# BrainA1-12n.net
KiCad netlist of a schematic drawn in EAGLE
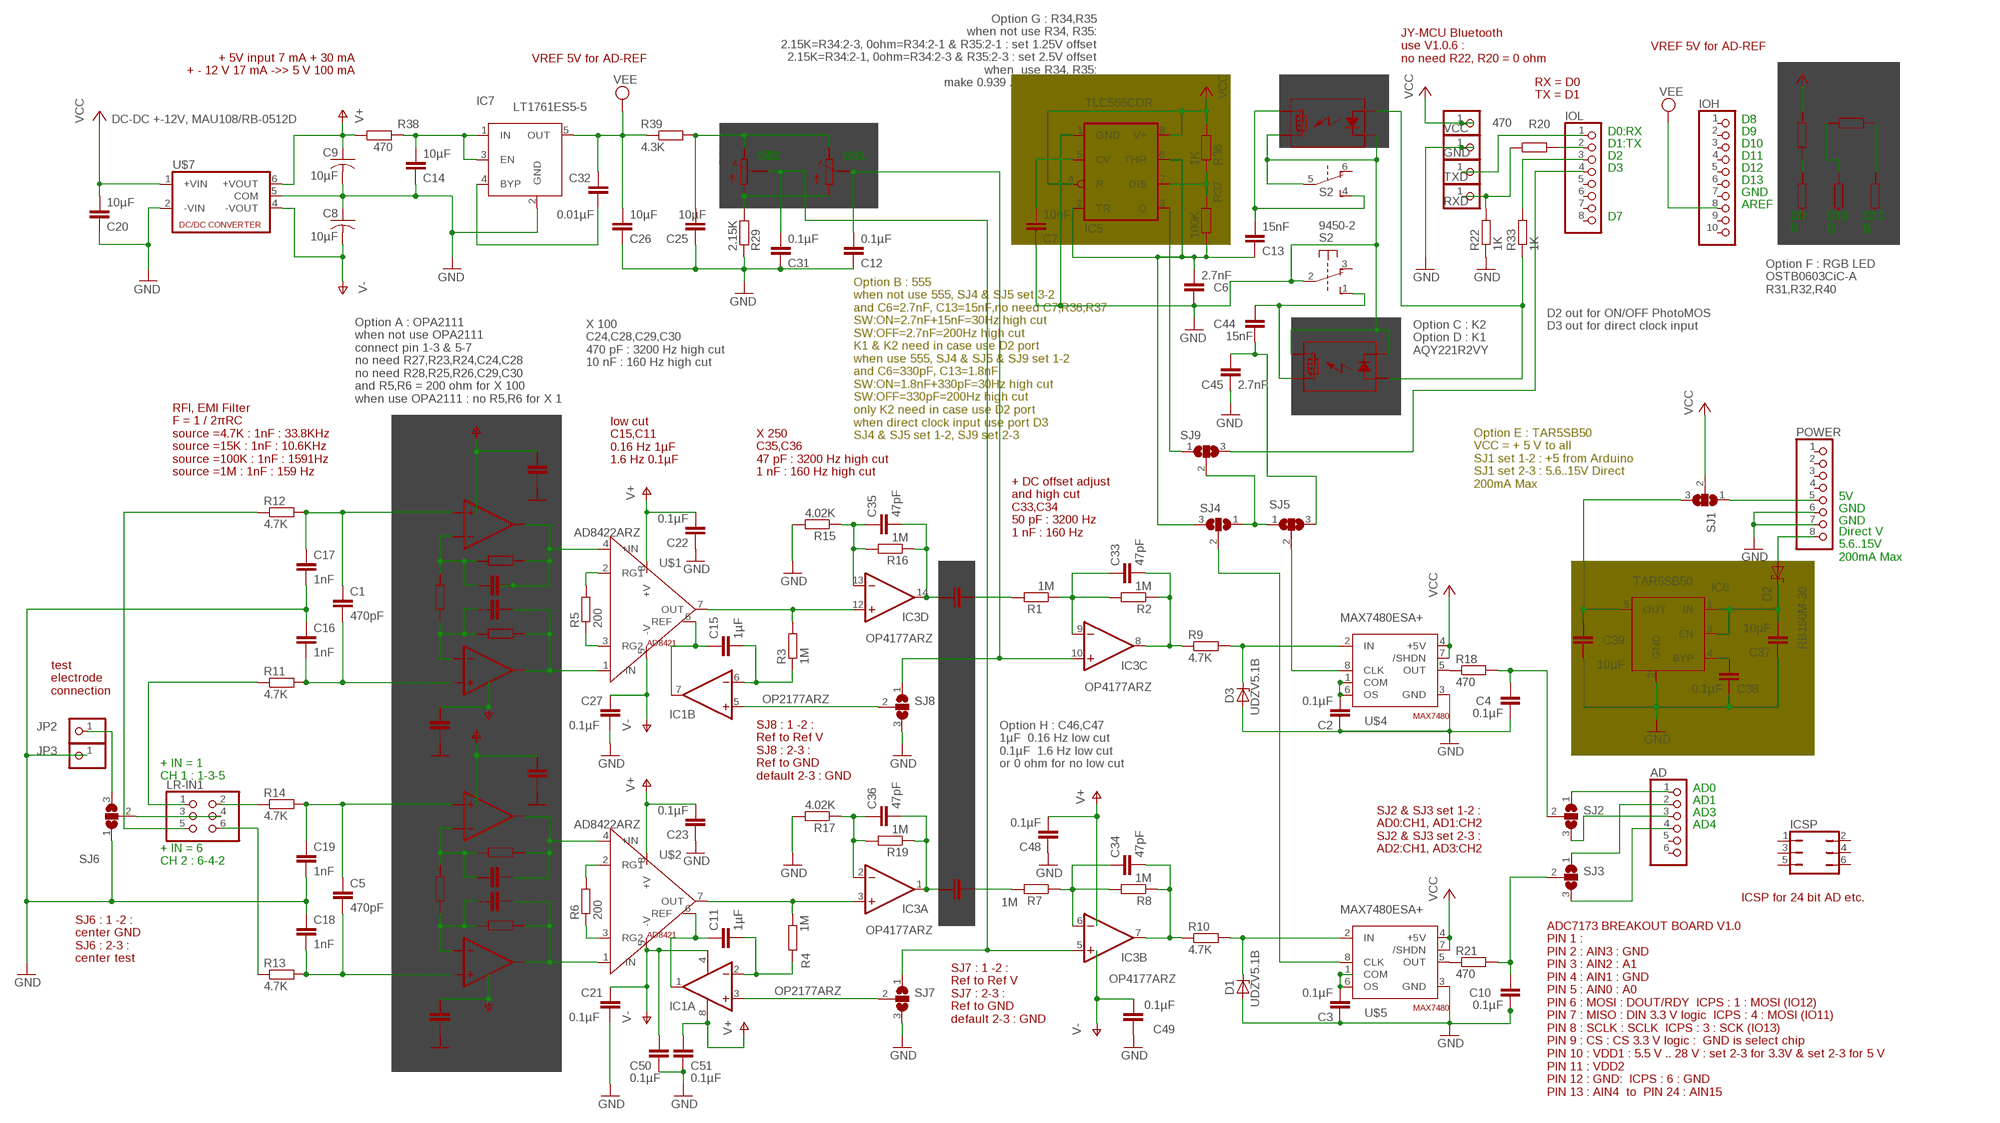
[diagram p0: schematic, sheet 1]

(export (version "E")
  (design (tool "Eeschema 10.0.6"))
  (components
    (comp (ref "AD")
      (value "PINHD-1X6")
      (footprint "eagle-import:1X06")
      (libsource (lib "eagle-import") (part "PINHD-1X6"))
    )
    (comp (ref "C1")
      (value "470pF")
      (footprint "eagle-import:C0805")
      (libsource (lib "eagle-import") (part "C-EUC0805"))
    )
    (comp (ref "C2")
      (value "0.1µF")
      (footprint "eagle-import:C0805")
      (libsource (lib "eagle-import") (part "C-EUC0805"))
    )
    (comp (ref "C3")
      (value "0.1µF")
      (footprint "eagle-import:C0805")
      (libsource (lib "eagle-import") (part "C-EUC0805"))
    )
    (comp (ref "C4")
      (value "0.1µF")
      (footprint "eagle-import:C0805")
      (libsource (lib "eagle-import") (part "C-EUC0805"))
    )
    (comp (ref "C5")
      (value "470pF")
      (footprint "eagle-import:C0805")
      (libsource (lib "eagle-import") (part "C-EUC0805"))
    )
    (comp (ref "C6")
      (value "2.7nF")
      (footprint "eagle-import:C0805")
      (libsource (lib "eagle-import") (part "C-EUC0805"))
    )
    (comp (ref "C7")
      (value "10nF")
      (footprint "eagle-import:C0805")
      (libsource (lib "eagle-import") (part "C-EUC0805"))
    )
    (comp (ref "C8")
      (value "10µF")
      (footprint "eagle-import:C0805")
      (libsource (lib "eagle-import") (part "C-USC0805"))
    )
    (comp (ref "C9")
      (value "10µF")
      (footprint "eagle-import:C0805")
      (libsource (lib "eagle-import") (part "C-USC0805"))
    )
    (comp (ref "C10")
      (value "0.1µF")
      (footprint "eagle-import:C0805")
      (libsource (lib "eagle-import") (part "C-EUC0805"))
    )
    (comp (ref "C11")
      (value "1µF")
      (footprint "eagle-import:C0805")
      (libsource (lib "eagle-import") (part "C-EUC0805"))
    )
    (comp (ref "C12")
      (value "0.1µF")
      (footprint "eagle-import:C0805")
      (libsource (lib "eagle-import") (part "C-EUC0805"))
    )
    (comp (ref "C13")
      (value "15nF")
      (footprint "eagle-import:C0805")
      (libsource (lib "eagle-import") (part "C-EUC0805"))
    )
    (comp (ref "C14")
      (value "10µF")
      (footprint "eagle-import:C0805")
      (libsource (lib "eagle-import") (part "C-EUC0805"))
    )
    (comp (ref "C15")
      (value "1µF")
      (footprint "eagle-import:C0805")
      (libsource (lib "eagle-import") (part "C-EUC0805"))
    )
    (comp (ref "C16")
      (value "1nF")
      (footprint "eagle-import:C0805")
      (libsource (lib "eagle-import") (part "C-EUC0805"))
    )
    (comp (ref "C17")
      (value "1nF")
      (footprint "eagle-import:C0805")
      (libsource (lib "eagle-import") (part "C-EUC0805"))
    )
    (comp (ref "C18")
      (value "1nF")
      (footprint "eagle-import:C0805")
      (libsource (lib "eagle-import") (part "C-EUC0805"))
    )
    (comp (ref "C19")
      (value "1nF")
      (footprint "eagle-import:C0805")
      (libsource (lib "eagle-import") (part "C-EUC0805"))
    )
    (comp (ref "C20")
      (value "10µF")
      (footprint "eagle-import:C0805")
      (libsource (lib "eagle-import") (part "C-EUC0805"))
    )
    (comp (ref "C21")
      (value "0.1µF")
      (footprint "eagle-import:C0805")
      (libsource (lib "eagle-import") (part "C-EUC0805"))
    )
    (comp (ref "C22")
      (value "0.1µF")
      (footprint "eagle-import:C0805")
      (libsource (lib "eagle-import") (part "C-EUC0805"))
    )
    (comp (ref "C23")
      (value "0.1µF")
      (footprint "eagle-import:C0805")
      (libsource (lib "eagle-import") (part "C-EUC0805"))
    )
    (comp (ref "C24")
      (value "470pF")
      (footprint "eagle-import:C0805")
      (libsource (lib "eagle-import") (part "C-EUC0805"))
    )
    (comp (ref "C25")
      (value "10µF")
      (footprint "eagle-import:C0805")
      (libsource (lib "eagle-import") (part "C-EUC0805"))
    )
    (comp (ref "C26")
      (value "10µF")
      (footprint "eagle-import:C0805")
      (libsource (lib "eagle-import") (part "C-EUC0805"))
    )
    (comp (ref "C27")
      (value "0.1µF")
      (footprint "eagle-import:C0805")
      (libsource (lib "eagle-import") (part "C-EUC0805"))
    )
    (comp (ref "C28")
      (value "470pF")
      (footprint "eagle-import:C0805")
      (libsource (lib "eagle-import") (part "C-EUC0805"))
    )
    (comp (ref "C29")
      (value "470pF")
      (footprint "eagle-import:C0805")
      (libsource (lib "eagle-import") (part "C-EUC0805"))
    )
    (comp (ref "C30")
      (value "470pF")
      (footprint "eagle-import:C0805")
      (libsource (lib "eagle-import") (part "C-EUC0805"))
    )
    (comp (ref "C31")
      (value "0.1µF")
      (footprint "eagle-import:C0805")
      (libsource (lib "eagle-import") (part "C-EUC0805"))
    )
    (comp (ref "C32")
      (value "0.01µF")
      (footprint "eagle-import:C0805")
      (libsource (lib "eagle-import") (part "C-EUC0805"))
    )
    (comp (ref "C33")
      (value "47pF")
      (footprint "eagle-import:C0805")
      (libsource (lib "eagle-import") (part "C-EUC0805"))
    )
    (comp (ref "C34")
      (value "47pF")
      (footprint "eagle-import:C0805")
      (libsource (lib "eagle-import") (part "C-EUC0805"))
    )
    (comp (ref "C35")
      (value "47pF")
      (footprint "eagle-import:C0805")
      (libsource (lib "eagle-import") (part "C-EUC0805"))
    )
    (comp (ref "C36")
      (value "47pF")
      (footprint "eagle-import:C0805")
      (libsource (lib "eagle-import") (part "C-EUC0805"))
    )
    (comp (ref "C37")
      (value "10µF")
      (footprint "eagle-import:C0805")
      (libsource (lib "eagle-import") (part "C-EUC0805"))
    )
    (comp (ref "C38")
      (value "0.1µF")
      (footprint "eagle-import:C0805")
      (libsource (lib "eagle-import") (part "C-EUC0805"))
    )
    (comp (ref "C39")
      (value "10µF")
      (footprint "eagle-import:C0805")
      (libsource (lib "eagle-import") (part "C-EUC0805"))
    )
    (comp (ref "C40")
      (value "0.1µF")
      (footprint "eagle-import:C0805")
      (libsource (lib "eagle-import") (part "C-EUC0805"))
    )
    (comp (ref "C41")
      (value "0.1µF")
      (footprint "eagle-import:C0805")
      (libsource (lib "eagle-import") (part "C-EUC0805"))
    )
    (comp (ref "C42")
      (value "0.1µF")
      (footprint "eagle-import:C0805")
      (libsource (lib "eagle-import") (part "C-EUC0805"))
    )
    (comp (ref "C43")
      (value "0.1µF")
      (footprint "eagle-import:C0805")
      (libsource (lib "eagle-import") (part "C-EUC0805"))
    )
    (comp (ref "C44")
      (value "15nF")
      (footprint "eagle-import:C0805")
      (libsource (lib "eagle-import") (part "C-EUC0805"))
    )
    (comp (ref "C45")
      (value "2.7nF")
      (footprint "eagle-import:C0805")
      (libsource (lib "eagle-import") (part "C-EUC0805"))
    )
    (comp (ref "C46")
      (value "1µF")
      (footprint "eagle-import:C0805")
      (libsource (lib "eagle-import") (part "C-EUC0805"))
    )
    (comp (ref "C47")
      (value "1µF")
      (footprint "eagle-import:C0805")
      (libsource (lib "eagle-import") (part "C-EUC0805"))
    )
    (comp (ref "C48")
      (value "0.1µF")
      (footprint "eagle-import:C0805")
      (libsource (lib "eagle-import") (part "C-EUC0805"))
    )
    (comp (ref "C49")
      (value "0.1µF")
      (footprint "eagle-import:C0805")
      (libsource (lib "eagle-import") (part "C-EUC0805"))
    )
    (comp (ref "C50")
      (value "0.1µF")
      (footprint "eagle-import:C0805")
      (libsource (lib "eagle-import") (part "C-EUC0805"))
    )
    (comp (ref "C51")
      (value "0.1µF")
      (footprint "eagle-import:C0805")
      (libsource (lib "eagle-import") (part "C-EUC0805"))
    )
    (comp (ref "D1")
      (value "UDZV5.1B")
      (footprint "eagle-import:SMB")
      (libsource (lib "eagle-import") (part "ZENER-DIODESMB"))
    )
    (comp (ref "D2")
      (value "RB160M-30")
      (footprint "eagle-import:POWERDI323")
      (libsource (lib "eagle-import") (part "PD3S160"))
    )
    (comp (ref "D3")
      (value "UDZV5.1B")
      (footprint "eagle-import:SMB")
      (libsource (lib "eagle-import") (part "ZENER-DIODESMB"))
    )
    (comp (ref "GND")
      (value "PINHD-1X1")
      (footprint "eagle-import:1X01")
      (libsource (lib "eagle-import") (part "PINHD-1X1"))
    )
    (comp (ref "IC1")
      (value "OP2177ARZ")
      (footprint "eagle-import:SOIC8")
      (libsource (lib "eagle-import") (part "OP1277R"))
    )
    (comp (ref "IC2")
      (value "OPA2111KP")
      (footprint "eagle-import:DIL08")
      (libsource (lib "eagle-import") (part "OPA2111P"))
    )
    (comp (ref "IC3")
      (value "OP4177ARZ")
      (footprint "eagle-import:SO14")
      (libsource (lib "eagle-import") (part "TL064D"))
    )
    (comp (ref "IC4")
      (value "OPA2111KP")
      (footprint "eagle-import:DIL08")
      (libsource (lib "eagle-import") (part "OPA2111P"))
    )
    (comp (ref "IC5")
      (value "TLC555CDR")
      (footprint "eagle-import:SO08")
      (libsource (lib "eagle-import") (part "555DLM"))
    )
    (comp (ref "IC6")
      (value "TAR5SB50")
      (footprint "eagle-import:SOT23-5")
      (libsource (lib "eagle-import") (part "MIC5219XX"))
    )
    (comp (ref "IC7")
      (value "LT1761ES5-5")
      (footprint "eagle-import:SOT23-5")
      (libsource (lib "eagle-import") (part "MIC5219XX"))
    )
    (comp (ref "ICSP")
      (value "JP3Q")
      (footprint "eagle-import:JP3Q")
      (libsource (lib "eagle-import") (part "JP3Q"))
    )
    (comp (ref "IOH")
      (value "PINHD-1X10")
      (footprint "eagle-import:1X10")
      (libsource (lib "eagle-import") (part "PINHD-1X10"))
    )
    (comp (ref "IOL")
      (value "PINHD-1X8")
      (footprint "eagle-import:1X08")
      (libsource (lib "eagle-import") (part "PINHD-1X8"))
    )
    (comp (ref "JP2")
      (value "PINHD-1X1")
      (footprint "eagle-import:1X01")
      (libsource (lib "eagle-import") (part "PINHD-1X1"))
    )
    (comp (ref "JP3")
      (value "PINHD-1X1")
      (footprint "eagle-import:1X01")
      (libsource (lib "eagle-import") (part "PINHD-1X1"))
    )
    (comp (ref "K1")
      (value "AQY221R2VY")
      (footprint "eagle-import:SSOP4")
      (fields (field (name "MF") "AROMAT/ MATSUSHITA") (field (name "MPN") "AQY221R2V"))
      (libsource (lib "eagle-import") (part "AQY2212VR"))
    )
    (comp (ref "K2")
      (value "AQY221R2VY")
      (footprint "eagle-import:SSOP4")
      (fields (field (name "MF") "AROMAT/ MATSUSHITA") (field (name "MPN") "AQY221R2V"))
      (libsource (lib "eagle-import") (part "AQY2212VR"))
    )
    (comp (ref "LR-IN1")
      (value "PINHD-2X3/90")
      (footprint "eagle-import:2X03_90")
      (libsource (lib "eagle-import") (part "PINHD-2X3/90"))
    )
    (comp (ref "POWER")
      (value "PINHD-1X8")
      (footprint "eagle-import:1X08")
      (libsource (lib "eagle-import") (part "PINHD-1X8"))
    )
    (comp (ref "R1")
      (value "1M")
      (footprint "eagle-import:R0805")
      (libsource (lib "eagle-import") (part "R-EU_R0805"))
    )
    (comp (ref "R2")
      (value "1M")
      (footprint "eagle-import:R0805")
      (libsource (lib "eagle-import") (part "R-EU_R0805"))
    )
    (comp (ref "R3")
      (value "1M")
      (footprint "eagle-import:R0805")
      (libsource (lib "eagle-import") (part "R-EU_R0805"))
    )
    (comp (ref "R4")
      (value "1M")
      (footprint "eagle-import:R0805")
      (libsource (lib "eagle-import") (part "R-EU_R0805"))
    )
    (comp (ref "R5")
      (value "200")
      (footprint "eagle-import:R0805")
      (libsource (lib "eagle-import") (part "R-EU_R0805"))
    )
    (comp (ref "R6")
      (value "200")
      (footprint "eagle-import:R0805")
      (libsource (lib "eagle-import") (part "R-EU_R0805"))
    )
    (comp (ref "R7")
      (value "1M")
      (footprint "eagle-import:R0805")
      (libsource (lib "eagle-import") (part "R-EU_R0805"))
    )
    (comp (ref "R8")
      (value "1M")
      (footprint "eagle-import:R0805")
      (libsource (lib "eagle-import") (part "R-EU_R0805"))
    )
    (comp (ref "R9")
      (value "4.7K")
      (footprint "eagle-import:R0805")
      (libsource (lib "eagle-import") (part "R-EU_R0805"))
    )
    (comp (ref "R10")
      (value "4.7K")
      (footprint "eagle-import:R0805")
      (libsource (lib "eagle-import") (part "R-EU_R0805"))
    )
    (comp (ref "R11")
      (value "4.7K")
      (footprint "eagle-import:R0805")
      (libsource (lib "eagle-import") (part "R-EU_R0805"))
    )
    (comp (ref "R12")
      (value "4.7K")
      (footprint "eagle-import:R0805")
      (libsource (lib "eagle-import") (part "R-EU_R0805"))
    )
    (comp (ref "R13")
      (value "4.7K")
      (footprint "eagle-import:R0805")
      (libsource (lib "eagle-import") (part "R-EU_R0805"))
    )
    (comp (ref "R14")
      (value "4.7K")
      (footprint "eagle-import:R0805")
      (libsource (lib "eagle-import") (part "R-EU_R0805"))
    )
    (comp (ref "R15")
      (value "4.02K")
      (footprint "eagle-import:R0805")
      (libsource (lib "eagle-import") (part "R-EU_R0805"))
    )
    (comp (ref "R16")
      (value "1M")
      (footprint "eagle-import:R0805")
      (libsource (lib "eagle-import") (part "R-EU_R0805"))
    )
    (comp (ref "R17")
      (value "4.02K")
      (footprint "eagle-import:R0805")
      (libsource (lib "eagle-import") (part "R-EU_R0805"))
    )
    (comp (ref "R18")
      (value "470")
      (footprint "eagle-import:R0805")
      (libsource (lib "eagle-import") (part "R-EU_R0805"))
    )
    (comp (ref "R19")
      (value "1M")
      (footprint "eagle-import:R0805")
      (libsource (lib "eagle-import") (part "R-EU_R0805"))
    )
    (comp (ref "R20")
      (value "470")
      (footprint "eagle-import:R0805")
      (libsource (lib "eagle-import") (part "R-EU_R0805"))
    )
    (comp (ref "R21")
      (value "470")
      (footprint "eagle-import:R0805")
      (libsource (lib "eagle-import") (part "R-EU_R0805"))
    )
    (comp (ref "R22")
      (value "1K")
      (footprint "eagle-import:R0805")
      (libsource (lib "eagle-import") (part "R-EU_R0805"))
    )
    (comp (ref "R23")
      (value "100K")
      (footprint "eagle-import:R0805")
      (libsource (lib "eagle-import") (part "R-EU_R0805"))
    )
    (comp (ref "R24")
      (value "100K")
      (footprint "eagle-import:R0805")
      (libsource (lib "eagle-import") (part "R-EU_R0805"))
    )
    (comp (ref "R25")
      (value "100K")
      (footprint "eagle-import:R0805")
      (libsource (lib "eagle-import") (part "R-EU_R0805"))
    )
    (comp (ref "R26")
      (value "100K")
      (footprint "eagle-import:R0805")
      (libsource (lib "eagle-import") (part "R-EU_R0805"))
    )
    (comp (ref "R27")
      (value "2K")
      (footprint "eagle-import:R0805")
      (libsource (lib "eagle-import") (part "R-EU_R0805"))
    )
    (comp (ref "R28")
      (value "2K")
      (footprint "eagle-import:R0805")
      (libsource (lib "eagle-import") (part "R-EU_R0805"))
    )
    (comp (ref "R29")
      (value "2.15K")
      (footprint "eagle-import:R0805")
      (libsource (lib "eagle-import") (part "R-EU_R0805"))
    )
    (comp (ref "R30")
      (value "LED")
      (footprint "eagle-import:R0402")
      (libsource (lib "eagle-import") (part "R-EU_R0402"))
    )
    (comp (ref "R31")
      (value "1K")
      (footprint "eagle-import:R0402")
      (libsource (lib "eagle-import") (part "R-EU_R0402"))
    )
    (comp (ref "R32")
      (value "1K")
      (footprint "eagle-import:R0402")
      (libsource (lib "eagle-import") (part "R-EU_R0402"))
    )
    (comp (ref "R33")
      (value "1K")
      (footprint "eagle-import:R0805")
      (libsource (lib "eagle-import") (part "R-EU_R0805"))
    )
    (comp (ref "R34")
      (value "10K")
      (footprint "eagle-import:RTRIM5X")
      (libsource (lib "eagle-import") (part "R-TRIMM5X"))
    )
    (comp (ref "R35")
      (value "10K")
      (footprint "eagle-import:RTRIM5X")
      (libsource (lib "eagle-import") (part "R-TRIMM5X"))
    )
    (comp (ref "R36")
      (value "1K")
      (footprint "eagle-import:R0805")
      (libsource (lib "eagle-import") (part "R-EU_R0805"))
    )
    (comp (ref "R37")
      (value "100K")
      (footprint "eagle-import:R0805")
      (libsource (lib "eagle-import") (part "R-EU_R0805"))
    )
    (comp (ref "R38")
      (value "470")
      (footprint "eagle-import:R0805")
      (libsource (lib "eagle-import") (part "R-EU_R0805"))
    )
    (comp (ref "R39")
      (value "4.3K")
      (footprint "eagle-import:R0805")
      (libsource (lib "eagle-import") (part "R-EU_R0805"))
    )
    (comp (ref "R40")
      (value "1K")
      (footprint "eagle-import:R0402")
      (libsource (lib "eagle-import") (part "R-EU_R0402"))
    )
    (comp (ref "R41")
      (value "LED")
      (footprint "eagle-import:R0402")
      (libsource (lib "eagle-import") (part "R-EU_R0402"))
    )
    (comp (ref "RXD")
      (value "PINHD-1X1")
      (footprint "eagle-import:1X01")
      (libsource (lib "eagle-import") (part "PINHD-1X1"))
    )
    (comp (ref "S2")
      (value "9450-2")
      (footprint "eagle-import:9450-2")
      (libsource (lib "eagle-import") (part "9450-2"))
    )
    (comp (ref "SJ1")
      (value "SJ2W")
      (footprint "eagle-import:SJ_2")
      (libsource (lib "eagle-import") (part "SJ2W"))
    )
    (comp (ref "SJ2")
      (value "SJ2W")
      (footprint "eagle-import:SJ_2")
      (libsource (lib "eagle-import") (part "SJ2W"))
    )
    (comp (ref "SJ3")
      (value "SJ2W")
      (footprint "eagle-import:SJ_2")
      (libsource (lib "eagle-import") (part "SJ2W"))
    )
    (comp (ref "SJ4")
      (value "SJ2W")
      (footprint "eagle-import:SJ_2")
      (libsource (lib "eagle-import") (part "SJ2W"))
    )
    (comp (ref "SJ5")
      (value "SJ2W")
      (footprint "eagle-import:SJ_2")
      (libsource (lib "eagle-import") (part "SJ2W"))
    )
    (comp (ref "SJ6")
      (value "SJ2W")
      (footprint "eagle-import:SJ_2")
      (libsource (lib "eagle-import") (part "SJ2W"))
    )
    (comp (ref "SJ7")
      (value "SJ2W")
      (footprint "eagle-import:SJ_2")
      (libsource (lib "eagle-import") (part "SJ2W"))
    )
    (comp (ref "SJ8")
      (value "SJ2W")
      (footprint "eagle-import:SJ_2")
      (libsource (lib "eagle-import") (part "SJ2W"))
    )
    (comp (ref "SJ9")
      (value "SJ2W")
      (footprint "eagle-import:SJ_2")
      (libsource (lib "eagle-import") (part "SJ2W"))
    )
    (comp (ref "TXD")
      (value "PINHD-1X1")
      (footprint "eagle-import:1X01")
      (libsource (lib "eagle-import") (part "PINHD-1X1"))
    )
    (comp (ref "U$1")
      (value "AD8422ARZ")
      (footprint "eagle-import:AD8421")
      (libsource (lib "eagle-import") (part "AD8421"))
    )
    (comp (ref "U$2")
      (value "AD8422ARZ")
      (footprint "eagle-import:AD8421")
      (libsource (lib "eagle-import") (part "AD8421"))
    )
    (comp (ref "U$4")
      (value "MAX7480ESA+")
      (footprint "eagle-import:MAX7480")
      (libsource (lib "eagle-import") (part "MAX7480"))
    )
    (comp (ref "U$5")
      (value "MAX7480ESA+")
      (footprint "eagle-import:MAX7480")
      (libsource (lib "eagle-import") (part "MAX7480"))
    )
    (comp (ref "U$7")
      (value "DC-DC +-12V, MAU108/RB-0512D")
      (footprint "eagle-import:RB-0515D")
      (libsource (lib "eagle-import") (part "RB-0515D"))
    )
    (comp (ref "VCC")
      (value "PINHD-1X1")
      (footprint "eagle-import:1X01")
      (libsource (lib "eagle-import") (part "PINHD-1X1"))
    )
  )
  (nets
    (net (code "1") (name "GND") (class "Default")
      (node (ref "C10") (pin "1") (pinfunction "1_1") (pintype "passive"))
      (node (ref "C12") (pin "1") (pinfunction "1_1") (pintype "passive"))
      (node (ref "C14") (pin "1") (pinfunction "1_1") (pintype "passive"))
      (node (ref "C16") (pin "1") (pinfunction "1_1") (pintype "passive"))
      (node (ref "C17") (pin "2") (pinfunction "2_2") (pintype "passive"))
      (node (ref "C18") (pin "1") (pinfunction "1_1") (pintype "passive"))
      (node (ref "C19") (pin "2") (pinfunction "2_2") (pintype "passive"))
      (node (ref "C2") (pin "1") (pinfunction "1_1") (pintype "passive"))
      (node (ref "C20") (pin "1") (pinfunction "1_1") (pintype "passive"))
      (node (ref "C21") (pin "2") (pinfunction "2_2") (pintype "passive"))
      (node (ref "C22") (pin "1") (pinfunction "1_1") (pintype "passive"))
      (node (ref "C23") (pin "1") (pinfunction "1_1") (pintype "passive"))
      (node (ref "C25") (pin "1") (pinfunction "1_1") (pintype "passive"))
      (node (ref "C26") (pin "1") (pinfunction "1_1") (pintype "passive"))
      (node (ref "C27") (pin "2") (pinfunction "2_2") (pintype "passive"))
      (node (ref "C3") (pin "1") (pinfunction "1_1") (pintype "passive"))
      (node (ref "C31") (pin "1") (pinfunction "1_1") (pintype "passive"))
      (node (ref "C37") (pin "1") (pinfunction "1_1") (pintype "passive"))
      (node (ref "C38") (pin "1") (pinfunction "1_1") (pintype "passive"))
      (node (ref "C39") (pin "1") (pinfunction "1_1") (pintype "passive"))
      (node (ref "C4") (pin "1") (pinfunction "1_1") (pintype "passive"))
      (node (ref "C40") (pin "1") (pinfunction "1_1") (pintype "passive"))
      (node (ref "C41") (pin "2") (pinfunction "2_2") (pintype "passive"))
      (node (ref "C42") (pin "2") (pinfunction "2_2") (pintype "passive"))
      (node (ref "C43") (pin "2") (pinfunction "2_2") (pintype "passive"))
      (node (ref "C45") (pin "1") (pinfunction "1_1") (pintype "passive"))
      (node (ref "C48") (pin "1") (pinfunction "1_1") (pintype "passive"))
      (node (ref "C49") (pin "1") (pinfunction "1_1") (pintype "passive"))
      (node (ref "C50") (pin "2") (pinfunction "2_2") (pintype "passive"))
      (node (ref "C51") (pin "2") (pinfunction "2_2") (pintype "passive"))
      (node (ref "C6") (pin "1") (pinfunction "1_1") (pintype "passive"))
      (node (ref "C7") (pin "1") (pinfunction "1_1") (pintype "passive"))
      (node (ref "C8") (pin "1") (pinfunction "1_1") (pintype "passive"))
      (node (ref "C9") (pin "2") (pinfunction "2_2") (pintype "passive"))
      (node (ref "D1") (pin "A") (pinfunction "A_A") (pintype "passive"))
      (node (ref "D3") (pin "A") (pinfunction "A_A") (pintype "passive"))
      (node (ref "GND") (pin "1") (pinfunction "1_1") (pintype "passive"))
      (node (ref "IC5") (pin "1") (pinfunction "GND_1") (pintype "power_in"))
      (node (ref "IC6") (pin "2") (pinfunction "GND_2") (pintype "power_in"))
      (node (ref "IC7") (pin "2") (pinfunction "GND_2") (pintype "power_in"))
      (node (ref "JP3") (pin "1") (pinfunction "1_1") (pintype "passive"))
      (node (ref "K1") (pin "2") (pinfunction "K_2") (pintype "passive"))
      (node (ref "K1") (pin "3") (pinfunction "DS2_3") (pintype "passive"))
      (node (ref "K2") (pin "2") (pinfunction "K_2") (pintype "passive"))
      (node (ref "K2") (pin "3") (pinfunction "DS2_3") (pintype "passive"))
      (node (ref "POWER") (pin "6") (pinfunction "6_6") (pintype "passive"))
      (node (ref "POWER") (pin "7") (pinfunction "7_7") (pintype "passive"))
      (node (ref "R15") (pin "2") (pinfunction "2_2") (pintype "passive"))
      (node (ref "R17") (pin "2") (pinfunction "2_2") (pintype "passive"))
      (node (ref "R22") (pin "1") (pinfunction "1_1") (pintype "passive"))
      (node (ref "R29") (pin "1") (pinfunction "1_1") (pintype "passive"))
      (node (ref "S2") (pin "2") (pinfunction "P_2") (pintype "passive"))
      (node (ref "S2") (pin "5") (pinfunction "P_5") (pintype "passive"))
      (node (ref "SJ6") (pin "1") (pinfunction "1_1") (pintype "passive"))
      (node (ref "SJ7") (pin "3") (pinfunction "3_3") (pintype "passive"))
      (node (ref "SJ8") (pin "3") (pinfunction "3_3") (pintype "passive"))
      (node (ref "U$4") (pin "3") (pinfunction "GND_3") (pintype "power_in"))
      (node (ref "U$5") (pin "3") (pinfunction "GND_3") (pintype "power_in"))
      (node (ref "U$7") (pin "2") (pinfunction "-VIN_2") (pintype "passive"))
      (node (ref "U$7") (pin "5") (pinfunction "COM_5") (pintype "passive"))
    )
    (net (code "2") (name "Net-(AD-Pad1)") (class "Default")
      (node (ref "AD") (pin "1") (pinfunction "1_1") (pintype "passive"))
      (node (ref "SJ2") (pin "1") (pinfunction "1_1") (pintype "passive"))
    )
    (net (code "3") (name "Net-(AD-Pad2)") (class "Default")
      (node (ref "AD") (pin "2") (pinfunction "2_2") (pintype "passive"))
      (node (ref "SJ3") (pin "1") (pinfunction "1_1") (pintype "passive"))
    )
    (net (code "4") (name "Net-(AD-Pad3)") (class "Default")
      (node (ref "AD") (pin "3") (pinfunction "3_3") (pintype "passive"))
      (node (ref "SJ2") (pin "3") (pinfunction "3_3") (pintype "passive"))
    )
    (net (code "5") (name "Net-(AD-Pad4)") (class "Default")
      (node (ref "AD") (pin "4") (pinfunction "4_4") (pintype "passive"))
      (node (ref "SJ3") (pin "3") (pinfunction "3_3") (pintype "passive"))
    )
    (net (code "6") (name "Net-(C4-Pad2)") (class "Default")
      (node (ref "C4") (pin "2") (pinfunction "2_2") (pintype "passive"))
      (node (ref "R18") (pin "2") (pinfunction "2_2") (pintype "passive"))
      (node (ref "SJ2") (pin "2") (pinfunction "2_2") (pintype "passive"))
    )
    (net (code "7") (name "Net-(C10-Pad2)") (class "Default")
      (node (ref "C10") (pin "2") (pinfunction "2_2") (pintype "passive"))
      (node (ref "R21") (pin "2") (pinfunction "2_2") (pintype "passive"))
      (node (ref "SJ3") (pin "2") (pinfunction "2_2") (pintype "passive"))
    )
    (net (code "8") (name "Net-(C44-Pad1)") (class "Default")
      (node (ref "C44") (pin "1") (pinfunction "1_1") (pintype "passive"))
      (node (ref "C45") (pin "2") (pinfunction "2_2") (pintype "passive"))
      (node (ref "SJ5") (pin "3") (pinfunction "3_3") (pintype "passive"))
    )
    (net (code "9") (name "Net-(C46-Pad2)") (class "Default")
      (node (ref "C46") (pin "2") (pinfunction "2_2") (pintype "passive"))
      (node (ref "R1") (pin "2") (pinfunction "2_2") (pintype "passive"))
    )
    (net (code "10") (name "Net-(C47-Pad2)") (class "Default")
      (node (ref "C47") (pin "2") (pinfunction "2_2") (pintype "passive"))
      (node (ref "R7") (pin "2") (pinfunction "2_2") (pintype "passive"))
    )
    (net (code "11") (name "Net-(D2-PadA)") (class "Default")
      (node (ref "D2") (pin "A") (pinfunction "A_A") (pintype "passive"))
      (node (ref "POWER") (pin "8") (pinfunction "8_8") (pintype "passive"))
    )
    (net (code "12") (name "Net-(IC1A-+IN)") (class "Default")
      (node (ref "IC1") (pin "3") (pinfunction "+IN_3") (pintype "input"))
      (node (ref "SJ7") (pin "2") (pinfunction "2_2") (pintype "passive"))
    )
    (net (code "13") (name "Net-(IC1A--IN)") (class "Default")
      (node (ref "C11") (pin "2") (pinfunction "2_2") (pintype "passive"))
      (node (ref "IC1") (pin "2") (pinfunction "-IN_2") (pintype "input"))
      (node (ref "R4") (pin "1") (pinfunction "1_1") (pintype "passive"))
    )
    (net (code "14") (name "Net-(IC1A-OUT)") (class "Default")
      (node (ref "C11") (pin "1") (pinfunction "1_1") (pintype "passive"))
      (node (ref "IC1") (pin "1") (pinfunction "OUT_1") (pintype "output"))
      (node (ref "U$2") (pin "6") (pinfunction "REF_6") (pintype "input"))
    )
    (net (code "15") (name "Net-(IC1B-+IN)") (class "Default")
      (node (ref "IC1") (pin "5") (pinfunction "+IN_5") (pintype "input"))
      (node (ref "SJ8") (pin "2") (pinfunction "2_2") (pintype "passive"))
    )
    (net (code "16") (name "Net-(IC1B--IN)") (class "Default")
      (node (ref "C15") (pin "2") (pinfunction "2_2") (pintype "passive"))
      (node (ref "IC1") (pin "6") (pinfunction "-IN_6") (pintype "input"))
      (node (ref "R3") (pin "1") (pinfunction "1_1") (pintype "passive"))
    )
    (net (code "17") (name "Net-(IC1B-OUT)") (class "Default")
      (node (ref "C15") (pin "1") (pinfunction "1_1") (pintype "passive"))
      (node (ref "IC1") (pin "7") (pinfunction "OUT_7") (pintype "output"))
      (node (ref "U$1") (pin "6") (pinfunction "REF_6") (pintype "input"))
    )
    (net (code "18") (name "Net-(IC2A-+IN)") (class "Default")
      (node (ref "C1") (pin "1") (pinfunction "1_1") (pintype "passive"))
      (node (ref "C17") (pin "1") (pinfunction "1_1") (pintype "passive"))
      (node (ref "IC2") (pin "3") (pinfunction "+IN_3") (pintype "input"))
      (node (ref "R12") (pin "2") (pinfunction "2_2") (pintype "passive"))
    )
    (net (code "19") (name "Net-(IC2A--IN)") (class "Default")
      (node (ref "C24") (pin "1") (pinfunction "1_1") (pintype "passive"))
      (node (ref "IC2") (pin "2") (pinfunction "-IN_2") (pintype "input"))
      (node (ref "R23") (pin "1") (pinfunction "1_1") (pintype "passive"))
      (node (ref "R27") (pin "2") (pinfunction "2_2") (pintype "passive"))
    )
    (net (code "20") (name "Net-(IC2A-OUT)") (class "Default")
      (node (ref "C24") (pin "2") (pinfunction "2_2") (pintype "passive"))
      (node (ref "IC2") (pin "1") (pinfunction "OUT_1") (pintype "output"))
      (node (ref "R23") (pin "2") (pinfunction "2_2") (pintype "passive"))
      (node (ref "U$1") (pin "4") (pinfunction "+IN_4") (pintype "input"))
    )
    (net (code "21") (name "Net-(IC2B-+IN)") (class "Default")
      (node (ref "C1") (pin "2") (pinfunction "2_2") (pintype "passive"))
      (node (ref "C16") (pin "2") (pinfunction "2_2") (pintype "passive"))
      (node (ref "IC2") (pin "5") (pinfunction "+IN_5") (pintype "input"))
      (node (ref "R11") (pin "2") (pinfunction "2_2") (pintype "passive"))
    )
    (net (code "22") (name "Net-(IC2B--IN)") (class "Default")
      (node (ref "C28") (pin "1") (pinfunction "1_1") (pintype "passive"))
      (node (ref "IC2") (pin "6") (pinfunction "-IN_6") (pintype "input"))
      (node (ref "R24") (pin "1") (pinfunction "1_1") (pintype "passive"))
      (node (ref "R27") (pin "1") (pinfunction "1_1") (pintype "passive"))
    )
    (net (code "23") (name "Net-(IC2B-OUT)") (class "Default")
      (node (ref "C28") (pin "2") (pinfunction "2_2") (pintype "passive"))
      (node (ref "IC2") (pin "7") (pinfunction "OUT_7") (pintype "output"))
      (node (ref "R24") (pin "2") (pinfunction "2_2") (pintype "passive"))
      (node (ref "U$1") (pin "1") (pinfunction "-IN_1") (pintype "passive"))
    )
    (net (code "24") (name "Net-(IC3A-+IN)") (class "Default")
      (node (ref "IC3") (pin "3") (pinfunction "+IN_3") (pintype "input"))
      (node (ref "R4") (pin "2") (pinfunction "2_2") (pintype "passive"))
      (node (ref "U$2") (pin "7") (pinfunction "OUT_7") (pintype "input"))
    )
    (net (code "25") (name "Net-(IC3A--IN)") (class "Default")
      (node (ref "C36") (pin "1") (pinfunction "1_1") (pintype "passive"))
      (node (ref "IC3") (pin "2") (pinfunction "-IN_2") (pintype "input"))
      (node (ref "R17") (pin "1") (pinfunction "1_1") (pintype "passive"))
      (node (ref "R19") (pin "2") (pinfunction "2_2") (pintype "passive"))
    )
    (net (code "26") (name "Net-(IC3A-OUT)") (class "Default")
      (node (ref "C36") (pin "2") (pinfunction "2_2") (pintype "passive"))
      (node (ref "C47") (pin "1") (pinfunction "1_1") (pintype "passive"))
      (node (ref "IC3") (pin "1") (pinfunction "OUT_1") (pintype "output"))
      (node (ref "R19") (pin "1") (pinfunction "1_1") (pintype "passive"))
    )
    (net (code "27") (name "Net-(IC3B-+IN)") (class "Default")
      (node (ref "C31") (pin "2") (pinfunction "2_2") (pintype "passive"))
      (node (ref "IC3") (pin "5") (pinfunction "+IN_5") (pintype "input"))
      (node (ref "R34") (pin "2") (pinfunction "S_2") (pintype "passive"))
      (node (ref "SJ7") (pin "1") (pinfunction "1_1") (pintype "passive"))
    )
    (net (code "28") (name "Net-(IC3B--IN)") (class "Default")
      (node (ref "C34") (pin "1") (pinfunction "1_1") (pintype "passive"))
      (node (ref "IC3") (pin "6") (pinfunction "-IN_6") (pintype "input"))
      (node (ref "R7") (pin "1") (pinfunction "1_1") (pintype "passive"))
      (node (ref "R8") (pin "2") (pinfunction "2_2") (pintype "passive"))
    )
    (net (code "29") (name "Net-(IC3B-OUT)") (class "Default")
      (node (ref "C34") (pin "2") (pinfunction "2_2") (pintype "passive"))
      (node (ref "IC3") (pin "7") (pinfunction "OUT_7") (pintype "output"))
      (node (ref "R10") (pin "1") (pinfunction "1_1") (pintype "passive"))
      (node (ref "R8") (pin "1") (pinfunction "1_1") (pintype "passive"))
    )
    (net (code "30") (name "Net-(IC3C-+IN)") (class "Default")
      (node (ref "C12") (pin "2") (pinfunction "2_2") (pintype "passive"))
      (node (ref "IC3") (pin "10") (pinfunction "+IN_10") (pintype "input"))
      (node (ref "R35") (pin "2") (pinfunction "S_2") (pintype "passive"))
      (node (ref "SJ8") (pin "1") (pinfunction "1_1") (pintype "passive"))
    )
    (net (code "31") (name "Net-(IC3C--IN)") (class "Default")
      (node (ref "C33") (pin "1") (pinfunction "1_1") (pintype "passive"))
      (node (ref "IC3") (pin "9") (pinfunction "-IN_9") (pintype "input"))
      (node (ref "R1") (pin "1") (pinfunction "1_1") (pintype "passive"))
      (node (ref "R2") (pin "2") (pinfunction "2_2") (pintype "passive"))
    )
    (net (code "32") (name "Net-(IC3C-OUT)") (class "Default")
      (node (ref "C33") (pin "2") (pinfunction "2_2") (pintype "passive"))
      (node (ref "IC3") (pin "8") (pinfunction "OUT_8") (pintype "output"))
      (node (ref "R2") (pin "1") (pinfunction "1_1") (pintype "passive"))
      (node (ref "R9") (pin "1") (pinfunction "1_1") (pintype "passive"))
    )
    (net (code "33") (name "Net-(IC3D-+IN)") (class "Default")
      (node (ref "IC3") (pin "12") (pinfunction "+IN_12") (pintype "input"))
      (node (ref "R3") (pin "2") (pinfunction "2_2") (pintype "passive"))
      (node (ref "U$1") (pin "7") (pinfunction "OUT_7") (pintype "input"))
    )
    (net (code "34") (name "Net-(IC3D--IN)") (class "Default")
      (node (ref "C35") (pin "1") (pinfunction "1_1") (pintype "passive"))
      (node (ref "IC3") (pin "13") (pinfunction "-IN_13") (pintype "input"))
      (node (ref "R15") (pin "1") (pinfunction "1_1") (pintype "passive"))
      (node (ref "R16") (pin "2") (pinfunction "2_2") (pintype "passive"))
    )
    (net (code "35") (name "Net-(IC3D-OUT)") (class "Default")
      (node (ref "C35") (pin "2") (pinfunction "2_2") (pintype "passive"))
      (node (ref "C46") (pin "1") (pinfunction "1_1") (pintype "passive"))
      (node (ref "IC3") (pin "14") (pinfunction "OUT_14") (pintype "output"))
      (node (ref "R16") (pin "1") (pinfunction "1_1") (pintype "passive"))
    )
    (net (code "36") (name "Net-(IC4A-+IN)") (class "Default")
      (node (ref "C19") (pin "1") (pinfunction "1_1") (pintype "passive"))
      (node (ref "C5") (pin "1") (pinfunction "1_1") (pintype "passive"))
      (node (ref "IC4") (pin "3") (pinfunction "+IN_3") (pintype "input"))
      (node (ref "R14") (pin "2") (pinfunction "2_2") (pintype "passive"))
    )
    (net (code "37") (name "Net-(IC4A--IN)") (class "Default")
      (node (ref "C29") (pin "1") (pinfunction "1_1") (pintype "passive"))
      (node (ref "IC4") (pin "2") (pinfunction "-IN_2") (pintype "input"))
      (node (ref "R25") (pin "1") (pinfunction "1_1") (pintype "passive"))
      (node (ref "R28") (pin "2") (pinfunction "2_2") (pintype "passive"))
    )
    (net (code "38") (name "Net-(IC4A-OUT)") (class "Default")
      (node (ref "C29") (pin "2") (pinfunction "2_2") (pintype "passive"))
      (node (ref "IC4") (pin "1") (pinfunction "OUT_1") (pintype "output"))
      (node (ref "R25") (pin "2") (pinfunction "2_2") (pintype "passive"))
      (node (ref "U$2") (pin "4") (pinfunction "+IN_4") (pintype "input"))
    )
    (net (code "39") (name "Net-(IC4B-+IN)") (class "Default")
      (node (ref "C18") (pin "2") (pinfunction "2_2") (pintype "passive"))
      (node (ref "C5") (pin "2") (pinfunction "2_2") (pintype "passive"))
      (node (ref "IC4") (pin "5") (pinfunction "+IN_5") (pintype "input"))
      (node (ref "R13") (pin "2") (pinfunction "2_2") (pintype "passive"))
    )
    (net (code "40") (name "Net-(IC4B--IN)") (class "Default")
      (node (ref "C30") (pin "1") (pinfunction "1_1") (pintype "passive"))
      (node (ref "IC4") (pin "6") (pinfunction "-IN_6") (pintype "input"))
      (node (ref "R26") (pin "1") (pinfunction "1_1") (pintype "passive"))
      (node (ref "R28") (pin "1") (pinfunction "1_1") (pintype "passive"))
    )
    (net (code "41") (name "Net-(IC4B-OUT)") (class "Default")
      (node (ref "C30") (pin "2") (pinfunction "2_2") (pintype "passive"))
      (node (ref "IC4") (pin "7") (pinfunction "OUT_7") (pintype "output"))
      (node (ref "R26") (pin "2") (pinfunction "2_2") (pintype "passive"))
      (node (ref "U$2") (pin "1") (pinfunction "-IN_1") (pintype "passive"))
    )
    (net (code "42") (name "Net-(IC5-CV)") (class "Default")
      (node (ref "C7") (pin "2") (pinfunction "2_2") (pintype "passive"))
      (node (ref "IC5") (pin "5") (pinfunction "CV_5") (pintype "input"))
    )
    (net (code "43") (name "Net-(IC5-DIS)") (class "Default")
      (node (ref "IC5") (pin "7") (pinfunction "DIS_7") (pintype "input"))
      (node (ref "R36") (pin "1") (pinfunction "1_1") (pintype "passive"))
      (node (ref "R37") (pin "2") (pinfunction "2_2") (pintype "passive"))
    )
    (net (code "44") (name "Net-(IC5-Q)") (class "Default")
      (node (ref "IC5") (pin "3") (pinfunction "Q_3") (pintype "output"))
      (node (ref "SJ9") (pin "1") (pinfunction "1_1") (pintype "passive"))
    )
    (net (code "45") (name "Net-(IC5-THR)") (class "Default")
      (node (ref "C13") (pin "1") (pinfunction "1_1") (pintype "passive"))
      (node (ref "C6") (pin "2") (pinfunction "2_2") (pintype "passive"))
      (node (ref "IC5") (pin "2") (pinfunction "TR_2") (pintype "input"))
      (node (ref "IC5") (pin "6") (pinfunction "THR_6") (pintype "input"))
      (node (ref "R37") (pin "1") (pinfunction "1_1") (pintype "passive"))
      (node (ref "SJ4") (pin "3") (pinfunction "3_3") (pintype "passive"))
    )
    (net (code "46") (name "Net-(IC6-BYP)") (class "Default")
      (node (ref "C38") (pin "2") (pinfunction "2_2") (pintype "passive"))
      (node (ref "IC6") (pin "4") (pinfunction "BYP_4") (pintype "passive"))
    )
    (net (code "47") (name "Net-(IC6-EN)") (class "Default")
      (node (ref "C37") (pin "2") (pinfunction "2_2") (pintype "passive"))
      (node (ref "D2") (pin "C") (pinfunction "C_C") (pintype "passive"))
      (node (ref "IC6") (pin "1") (pinfunction "IN_1") (pintype "input"))
      (node (ref "IC6") (pin "3") (pinfunction "EN_3") (pintype "input"))
    )
    (net (code "48") (name "Net-(IC6-OUT)") (class "Default")
      (node (ref "C39") (pin "2") (pinfunction "2_2") (pintype "passive"))
      (node (ref "IC6") (pin "5") (pinfunction "OUT_5") (pintype "output"))
      (node (ref "SJ1") (pin "3") (pinfunction "3_3") (pintype "passive"))
    )
    (net (code "49") (name "Net-(IC7-BYP)") (class "Default")
      (node (ref "C32") (pin "1") (pinfunction "1_1") (pintype "passive"))
      (node (ref "IC7") (pin "4") (pinfunction "BYP_4") (pintype "passive"))
    )
    (net (code "50") (name "Net-(IC7-EN)") (class "Default")
      (node (ref "C14") (pin "2") (pinfunction "2_2") (pintype "passive"))
      (node (ref "IC7") (pin "1") (pinfunction "IN_1") (pintype "input"))
      (node (ref "IC7") (pin "3") (pinfunction "EN_3") (pintype "input"))
      (node (ref "R38") (pin "2") (pinfunction "2_2") (pintype "passive"))
    )
    (net (code "51") (name "Net-(IOL-Pad1)") (class "Default")
      (node (ref "IOL") (pin "1") (pinfunction "1_1") (pintype "passive"))
      (node (ref "TXD") (pin "1") (pinfunction "1_1") (pintype "passive"))
    )
    (net (code "52") (name "Net-(IOL-Pad2)") (class "Default")
      (node (ref "IOL") (pin "2") (pinfunction "2_2") (pintype "passive"))
      (node (ref "R20") (pin "2") (pinfunction "2_2") (pintype "passive"))
    )
    (net (code "53") (name "Net-(IOL-Pad3)") (class "Default")
      (node (ref "IOL") (pin "3") (pinfunction "3_3") (pintype "passive"))
      (node (ref "R33") (pin "2") (pinfunction "2_2") (pintype "passive"))
    )
    (net (code "54") (name "Net-(IOL-Pad4)") (class "Default")
      (node (ref "IOL") (pin "4") (pinfunction "4_4") (pintype "passive"))
      (node (ref "SJ9") (pin "3") (pinfunction "3_3") (pintype "passive"))
    )
    (net (code "55") (name "Net-(JP2-Pad1)") (class "Default")
      (node (ref "JP2") (pin "1") (pinfunction "1_1") (pintype "passive"))
      (node (ref "SJ6") (pin "3") (pinfunction "3_3") (pintype "passive"))
    )
    (net (code "56") (name "Net-(K1-A)") (class "Default")
      (node (ref "K1") (pin "1") (pinfunction "A_1") (pintype "passive"))
      (node (ref "K2") (pin "1") (pinfunction "A_1") (pintype "passive"))
      (node (ref "R33") (pin "1") (pinfunction "1_1") (pintype "passive"))
    )
    (net (code "57") (name "Net-(K1-DS1)") (class "Default")
      (node (ref "C44") (pin "2") (pinfunction "2_2") (pintype "passive"))
      (node (ref "K1") (pin "4") (pinfunction "DS1_4") (pintype "passive"))
      (node (ref "S2") (pin "1") (pinfunction "S_1") (pintype "passive"))
    )
    (net (code "58") (name "Net-(K2-DS1)") (class "Default")
      (node (ref "C13") (pin "2") (pinfunction "2_2") (pintype "passive"))
      (node (ref "K2") (pin "4") (pinfunction "DS1_4") (pintype "passive"))
      (node (ref "S2") (pin "4") (pinfunction "S_4") (pintype "passive"))
    )
    (net (code "59") (name "Net-(LR-IN1-Pad1)") (class "Default")
      (node (ref "LR-IN1") (pin "1") (pinfunction "1_1") (pintype "passive"))
      (node (ref "R11") (pin "1") (pinfunction "1_1") (pintype "passive"))
    )
    (net (code "60") (name "Net-(LR-IN1-Pad2)") (class "Default")
      (node (ref "LR-IN1") (pin "2") (pinfunction "2_2") (pintype "passive"))
      (node (ref "R14") (pin "1") (pinfunction "1_1") (pintype "passive"))
    )
    (net (code "61") (name "Net-(LR-IN1-Pad3)") (class "Default")
      (node (ref "LR-IN1") (pin "3") (pinfunction "3_3") (pintype "passive"))
      (node (ref "LR-IN1") (pin "4") (pinfunction "4_4") (pintype "passive"))
      (node (ref "SJ6") (pin "2") (pinfunction "2_2") (pintype "passive"))
    )
    (net (code "62") (name "Net-(LR-IN1-Pad5)") (class "Default")
      (node (ref "LR-IN1") (pin "5") (pinfunction "5_5") (pintype "passive"))
      (node (ref "R12") (pin "1") (pinfunction "1_1") (pintype "passive"))
    )
    (net (code "63") (name "Net-(LR-IN1-Pad6)") (class "Default")
      (node (ref "LR-IN1") (pin "6") (pinfunction "6_6") (pintype "passive"))
      (node (ref "R13") (pin "1") (pinfunction "1_1") (pintype "passive"))
    )
    (net (code "64") (name "Net-(POWER-Pad5)") (class "Default")
      (node (ref "POWER") (pin "5") (pinfunction "5_5") (pintype "passive"))
      (node (ref "SJ1") (pin "1") (pinfunction "1_1") (pintype "passive"))
    )
    (net (code "65") (name "Net-(R20-Pad1)") (class "Default")
      (node (ref "R20") (pin "1") (pinfunction "1_1") (pintype "passive"))
      (node (ref "R22") (pin "2") (pinfunction "2_2") (pintype "passive"))
      (node (ref "RXD") (pin "1") (pinfunction "1_1") (pintype "passive"))
    )
    (net (code "66") (name "Net-(R30-Pad1)") (class "Default")
      (node (ref "R30") (pin "1") (pinfunction "1_1") (pintype "passive"))
      (node (ref "R40") (pin "2") (pinfunction "2_2") (pintype "passive"))
    )
    (net (code "67") (name "Net-(R30-Pad2)") (class "Default")
      (node (ref "R30") (pin "2") (pinfunction "2_2") (pintype "passive"))
      (node (ref "R32") (pin "2") (pinfunction "2_2") (pintype "passive"))
    )
    (net (code "68") (name "Net-(R31-Pad2)") (class "Default")
      (node (ref "R31") (pin "2") (pinfunction "2_2") (pintype "passive"))
      (node (ref "R41") (pin "1") (pinfunction "1_1") (pintype "passive"))
    )
    (net (code "69") (name "Net-(R34-A)") (class "Default")
      (node (ref "C25") (pin "2") (pinfunction "2_2") (pintype "passive"))
      (node (ref "R34") (pin "3") (pinfunction "A_3") (pintype "passive"))
      (node (ref "R35") (pin "3") (pinfunction "A_3") (pintype "passive"))
      (node (ref "R39") (pin "2") (pinfunction "2_2") (pintype "passive"))
    )
    (net (code "70") (name "Net-(R34-E)") (class "Default")
      (node (ref "R29") (pin "2") (pinfunction "2_2") (pintype "passive"))
      (node (ref "R34") (pin "1") (pinfunction "E_1") (pintype "passive"))
      (node (ref "R35") (pin "1") (pinfunction "E_1") (pintype "passive"))
    )
    (net (code "71") (name "Net-(SJ4-Pad1)") (class "Default")
      (node (ref "SJ4") (pin "1") (pinfunction "1_1") (pintype "passive"))
      (node (ref "SJ5") (pin "1") (pinfunction "1_1") (pintype "passive"))
      (node (ref "SJ9") (pin "2") (pinfunction "2_2") (pintype "passive"))
    )
    (net (code "72") (name "Net-(U$1-RG1)") (class "Default")
      (node (ref "R5") (pin "2") (pinfunction "2_2") (pintype "passive"))
      (node (ref "U$1") (pin "2") (pinfunction "RG1_2") (pintype "input"))
    )
    (net (code "73") (name "Net-(U$1-RG2)") (class "Default")
      (node (ref "R5") (pin "1") (pinfunction "1_1") (pintype "passive"))
      (node (ref "U$1") (pin "3") (pinfunction "RG2_3") (pintype "input"))
    )
    (net (code "74") (name "Net-(U$2-RG1)") (class "Default")
      (node (ref "R6") (pin "2") (pinfunction "2_2") (pintype "passive"))
      (node (ref "U$2") (pin "2") (pinfunction "RG1_2") (pintype "input"))
    )
    (net (code "75") (name "Net-(U$2-RG2)") (class "Default")
      (node (ref "R6") (pin "1") (pinfunction "1_1") (pintype "passive"))
      (node (ref "U$2") (pin "3") (pinfunction "RG2_3") (pintype "input"))
    )
    (net (code "76") (name "Net-(U$4-CLK)") (class "Default")
      (node (ref "SJ5") (pin "2") (pinfunction "2_2") (pintype "passive"))
      (node (ref "U$4") (pin "8") (pinfunction "CLK_8") (pintype "input"))
    )
    (net (code "77") (name "Net-(U$4-COM)") (class "Default")
      (node (ref "C2") (pin "2") (pinfunction "2_2") (pintype "passive"))
      (node (ref "U$4") (pin "1") (pinfunction "COM_1") (pintype "input"))
      (node (ref "U$4") (pin "6") (pinfunction "OS_6") (pintype "passive"))
    )
    (net (code "78") (name "Net-(U$4-IN)") (class "Default")
      (node (ref "D3") (pin "C") (pinfunction "C_C") (pintype "passive"))
      (node (ref "R9") (pin "2") (pinfunction "2_2") (pintype "passive"))
      (node (ref "U$4") (pin "2") (pinfunction "IN_2") (pintype "input"))
    )
    (net (code "79") (name "Net-(U$4-OUT)") (class "Default")
      (node (ref "R18") (pin "1") (pinfunction "1_1") (pintype "passive"))
      (node (ref "U$4") (pin "5") (pinfunction "OUT_5") (pintype "input"))
    )
    (net (code "80") (name "Net-(U$5-CLK)") (class "Default")
      (node (ref "SJ4") (pin "2") (pinfunction "2_2") (pintype "passive"))
      (node (ref "U$5") (pin "8") (pinfunction "CLK_8") (pintype "input"))
    )
    (net (code "81") (name "Net-(U$5-COM)") (class "Default")
      (node (ref "C3") (pin "2") (pinfunction "2_2") (pintype "passive"))
      (node (ref "U$5") (pin "1") (pinfunction "COM_1") (pintype "input"))
      (node (ref "U$5") (pin "6") (pinfunction "OS_6") (pintype "passive"))
    )
    (net (code "82") (name "Net-(U$5-IN)") (class "Default")
      (node (ref "D1") (pin "C") (pinfunction "C_C") (pintype "passive"))
      (node (ref "R10") (pin "2") (pinfunction "2_2") (pintype "passive"))
      (node (ref "U$5") (pin "2") (pinfunction "IN_2") (pintype "input"))
    )
    (net (code "83") (name "Net-(U$5-OUT)") (class "Default")
      (node (ref "R21") (pin "1") (pinfunction "1_1") (pintype "passive"))
      (node (ref "U$5") (pin "5") (pinfunction "OUT_5") (pintype "input"))
    )
    (net (code "84") (name "V+") (class "Default")
      (node (ref "C22") (pin "2") (pinfunction "2_2") (pintype "passive"))
      (node (ref "C23") (pin "2") (pinfunction "2_2") (pintype "passive"))
      (node (ref "C40") (pin "2") (pinfunction "2_2") (pintype "passive"))
      (node (ref "C42") (pin "1") (pinfunction "1_1") (pintype "passive"))
      (node (ref "C48") (pin "2") (pinfunction "2_2") (pintype "passive"))
      (node (ref "C51") (pin "1") (pinfunction "1_1") (pintype "passive"))
      (node (ref "C9") (pin "1") (pinfunction "1_1") (pintype "passive"))
      (node (ref "IC1") (pin "8") (pinfunction "V+_8") (pintype "power_in"))
      (node (ref "R38") (pin "1") (pinfunction "1_1") (pintype "passive"))
      (node (ref "U$1") (pin "8") (pinfunction "+V_8") (pintype "power_in"))
      (node (ref "U$2") (pin "8") (pinfunction "+V_8") (pintype "power_in"))
      (node (ref "U$7") (pin "6") (pinfunction "+VOUT_6") (pintype "passive"))
    )
    (net (code "85") (name "V-") (class "Default")
      (node (ref "C21") (pin "1") (pinfunction "1_1") (pintype "passive"))
      (node (ref "C27") (pin "1") (pinfunction "1_1") (pintype "passive"))
      (node (ref "C41") (pin "1") (pinfunction "1_1") (pintype "passive"))
      (node (ref "C43") (pin "1") (pinfunction "1_1") (pintype "passive"))
      (node (ref "C49") (pin "2") (pinfunction "2_2") (pintype "passive"))
      (node (ref "C50") (pin "1") (pinfunction "1_1") (pintype "passive"))
      (node (ref "C8") (pin "2") (pinfunction "2_2") (pintype "passive"))
      (node (ref "IC1") (pin "4") (pinfunction "V-_4") (pintype "power_in"))
      (node (ref "U$1") (pin "5") (pinfunction "-V_5") (pintype "power_in"))
      (node (ref "U$2") (pin "5") (pinfunction "-V_5") (pintype "power_in"))
      (node (ref "U$7") (pin "4") (pinfunction "-VOUT_4") (pintype "passive"))
    )
    (net (code "86") (name "VCC") (class "Default")
      (node (ref "C20") (pin "2") (pinfunction "2_2") (pintype "passive"))
      (node (ref "IC5") (pin "4") (pinfunction "R_4") (pintype "input"))
      (node (ref "IC5") (pin "8") (pinfunction "V+_8") (pintype "power_in"))
      (node (ref "R36") (pin "2") (pinfunction "2_2") (pintype "passive"))
      (node (ref "R41") (pin "2") (pinfunction "2_2") (pintype "passive"))
      (node (ref "SJ1") (pin "2") (pinfunction "2_2") (pintype "passive"))
      (node (ref "U$4") (pin "4") (pinfunction "+5V_4") (pintype "power_in"))
      (node (ref "U$4") (pin "7") (pinfunction "/SHDN_7") (pintype "input"))
      (node (ref "U$5") (pin "4") (pinfunction "+5V_4") (pintype "power_in"))
      (node (ref "U$5") (pin "7") (pinfunction "/SHDN_7") (pintype "input"))
      (node (ref "U$7") (pin "1") (pinfunction "+VIN_1") (pintype "passive"))
      (node (ref "VCC") (pin "1") (pinfunction "1_1") (pintype "passive"))
    )
    (net (code "87") (name "VEE") (class "Default")
      (node (ref "C26") (pin "2") (pinfunction "2_2") (pintype "passive"))
      (node (ref "C32") (pin "2") (pinfunction "2_2") (pintype "passive"))
      (node (ref "IC7") (pin "5") (pinfunction "OUT_5") (pintype "output"))
      (node (ref "IOH") (pin "8") (pinfunction "8_8") (pintype "passive"))
      (node (ref "R39") (pin "1") (pinfunction "1_1") (pintype "passive"))
    )
    (net (code "88") (name "unconnected-(AD-Pad5)") (class "Default")
      (node (ref "AD") (pin "5") (pinfunction "5_5") (pintype "passive"))
    )
    (net (code "89") (name "unconnected-(AD-Pad6)") (class "Default")
      (node (ref "AD") (pin "6") (pinfunction "6_6") (pintype "passive"))
    )
    (net (code "90") (name "unconnected-(ICSP-Pad1)") (class "Default")
      (node (ref "ICSP") (pin "1") (pinfunction "1_1") (pintype "passive"))
    )
    (net (code "91") (name "unconnected-(ICSP-Pad2)") (class "Default")
      (node (ref "ICSP") (pin "2") (pinfunction "2_2") (pintype "passive"))
    )
    (net (code "92") (name "unconnected-(ICSP-Pad3)") (class "Default")
      (node (ref "ICSP") (pin "3") (pinfunction "3_3") (pintype "passive"))
    )
    (net (code "93") (name "unconnected-(ICSP-Pad4)") (class "Default")
      (node (ref "ICSP") (pin "4") (pinfunction "4_4") (pintype "passive"))
    )
    (net (code "94") (name "unconnected-(ICSP-Pad5)") (class "Default")
      (node (ref "ICSP") (pin "5") (pinfunction "5_5") (pintype "passive"))
    )
    (net (code "95") (name "unconnected-(ICSP-Pad6)") (class "Default")
      (node (ref "ICSP") (pin "6") (pinfunction "6_6") (pintype "passive"))
    )
    (net (code "96") (name "unconnected-(IOH-Pad1)") (class "Default")
      (node (ref "IOH") (pin "1") (pinfunction "1_1") (pintype "passive"))
    )
    (net (code "97") (name "unconnected-(IOH-Pad2)") (class "Default")
      (node (ref "IOH") (pin "2") (pinfunction "2_2") (pintype "passive"))
    )
    (net (code "98") (name "unconnected-(IOH-Pad3)") (class "Default")
      (node (ref "IOH") (pin "3") (pinfunction "3_3") (pintype "passive"))
    )
    (net (code "99") (name "unconnected-(IOH-Pad4)") (class "Default")
      (node (ref "IOH") (pin "4") (pinfunction "4_4") (pintype "passive"))
    )
    (net (code "100") (name "unconnected-(IOH-Pad5)") (class "Default")
      (node (ref "IOH") (pin "5") (pinfunction "5_5") (pintype "passive"))
    )
    (net (code "101") (name "unconnected-(IOH-Pad6)") (class "Default")
      (node (ref "IOH") (pin "6") (pinfunction "6_6") (pintype "passive"))
    )
    (net (code "102") (name "unconnected-(IOH-Pad7)") (class "Default")
      (node (ref "IOH") (pin "7") (pinfunction "7_7") (pintype "passive"))
    )
    (net (code "103") (name "unconnected-(IOH-Pad9)") (class "Default")
      (node (ref "IOH") (pin "9") (pinfunction "9_9") (pintype "passive"))
    )
    (net (code "104") (name "unconnected-(IOH-Pad10)") (class "Default")
      (node (ref "IOH") (pin "10") (pinfunction "10_10") (pintype "passive"))
    )
    (net (code "105") (name "unconnected-(IOL-Pad5)") (class "Default")
      (node (ref "IOL") (pin "5") (pinfunction "5_5") (pintype "passive"))
    )
    (net (code "106") (name "unconnected-(IOL-Pad6)") (class "Default")
      (node (ref "IOL") (pin "6") (pinfunction "6_6") (pintype "passive"))
    )
    (net (code "107") (name "unconnected-(IOL-Pad7)") (class "Default")
      (node (ref "IOL") (pin "7") (pinfunction "7_7") (pintype "passive"))
    )
    (net (code "108") (name "unconnected-(IOL-Pad8)") (class "Default")
      (node (ref "IOL") (pin "8") (pinfunction "8_8") (pintype "passive"))
    )
    (net (code "109") (name "unconnected-(POWER-Pad1)") (class "Default")
      (node (ref "POWER") (pin "1") (pinfunction "1_1") (pintype "passive"))
    )
    (net (code "110") (name "unconnected-(POWER-Pad2)") (class "Default")
      (node (ref "POWER") (pin "2") (pinfunction "2_2") (pintype "passive"))
    )
    (net (code "111") (name "unconnected-(POWER-Pad3)") (class "Default")
      (node (ref "POWER") (pin "3") (pinfunction "3_3") (pintype "passive"))
    )
    (net (code "112") (name "unconnected-(POWER-Pad4)") (class "Default")
      (node (ref "POWER") (pin "4") (pinfunction "4_4") (pintype "passive"))
    )
    (net (code "113") (name "unconnected-(R31-Pad1)") (class "Default")
      (node (ref "R31") (pin "1") (pinfunction "1_1") (pintype "passive"))
    )
    (net (code "114") (name "unconnected-(R32-Pad1)") (class "Default")
      (node (ref "R32") (pin "1") (pinfunction "1_1") (pintype "passive"))
    )
    (net (code "115") (name "unconnected-(R40-Pad1)") (class "Default")
      (node (ref "R40") (pin "1") (pinfunction "1_1") (pintype "passive"))
    )
    (net (code "116") (name "unconnected-(S2A-O-Pad3)") (class "Default")
      (node (ref "S2") (pin "3") (pinfunction "O_3") (pintype "passive"))
    )
    (net (code "117") (name "unconnected-(S2B-O-Pad6)") (class "Default")
      (node (ref "S2") (pin "6") (pinfunction "O_6") (pintype "passive"))
    )
  )
)
